# 0033.net
KiCad netlist of a schematic drawn in Altium Designer
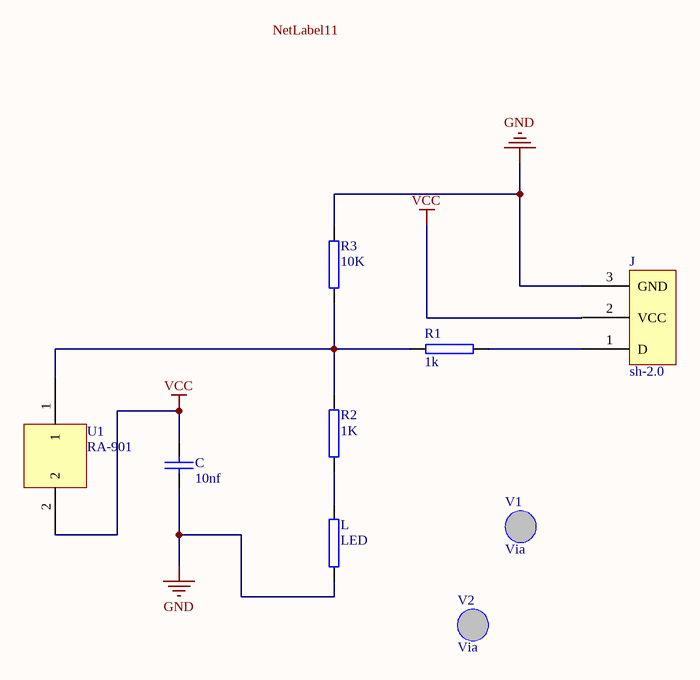
[diagram p0: 0033.SchDoc]

(export (version "E")
  (design (tool "Eeschema 10.0.6"))
  (components
    (comp (ref "C") (value "10nf") (footprint "0402") (libsource (lib "gupeng_sch") (part "CAP0402")))
    (comp (ref "J") (value "sh-2.0") (footprint "sh-2.0") (libsource (lib "jiumei") (part "sh-2.0")))
    (comp (ref "L") (value "LED") (footprint "0402") (libsource (lib "gupeng_sch") (part "RES0402")))
    (comp (ref "R1") (value "1k") (footprint "0402") (libsource (lib "gupeng_sch") (part "RES0402")))
    (comp (ref "R2") (value "1K") (footprint "0402") (libsource (lib "gupeng_sch") (part "RES0402")))
    (comp (ref "R3") (value "10K") (footprint "0402") (libsource (lib "gupeng_sch") (part "RES0402")))
    (comp (ref "U1") (value "RA-901") (footprint "RA-901") (libsource (lib "jiumei") (part "RA-901")))
    (comp (ref "V1") (value "Via") (footprint "zhaoyujiu:Via") (libsource (lib "zhaoyujiu") (part "Via")))
    (comp (ref "V2") (value "Via") (footprint "zhaoyujiu:Via") (libsource (lib "zhaoyujiu") (part "Via")))
  )
  (nets
    (net (code "2") (name "GND") (class "Default")
      (node (ref "C") (pin "2") (pinfunction "2_2") (pintype "passive"))
      (node (ref "J") (pin "3") (pinfunction "GND_3") (pintype "passive"))
      (node (ref "L") (pin "1") (pinfunction "1_1") (pintype "passive"))
      (node (ref "R3") (pin "2") (pinfunction "2_2") (pintype "passive"))
    )
    (net (code "3") (name "Net-(J-D)") (class "Default")
      (node (ref "J") (pin "1") (pinfunction "D_1") (pintype "passive"))
      (node (ref "R1") (pin "2") (pinfunction "2_2") (pintype "passive"))
    )
    (net (code "4") (name "Net-(L-Pad2)") (class "Default")
      (node (ref "L") (pin "2") (pinfunction "2_2") (pintype "passive"))
      (node (ref "R2") (pin "1") (pinfunction "1_1") (pintype "passive"))
    )
    (net (code "5") (name "Net-(R1-Pad1)") (class "Default")
      (node (ref "R1") (pin "1") (pinfunction "1_1") (pintype "passive"))
      (node (ref "R2") (pin "2") (pinfunction "2_2") (pintype "passive"))
      (node (ref "R3") (pin "1") (pinfunction "1_1") (pintype "passive"))
      (node (ref "U1") (pin "1") (pinfunction "1_1") (pintype "passive"))
    )
    (net (code "6") (name "VCC") (class "Default")
      (node (ref "C") (pin "1") (pinfunction "1_1") (pintype "passive"))
      (node (ref "J") (pin "2") (pinfunction "VCC_2") (pintype "passive"))
      (node (ref "U1") (pin "2") (pinfunction "2_2") (pintype "passive"))
    )
  )
)
